# 11_-BATTERY_BACKUP.net
KiCad netlist of a schematic drawn in Altium Designer
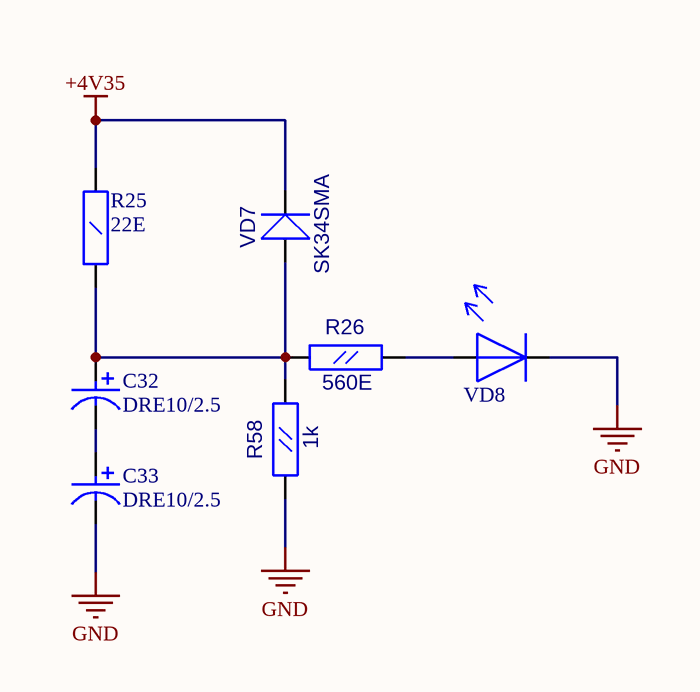
[diagram p0: [11]-BATTERY_BACKUP.SchDoc]

(export (version "E")
  (design (tool "Eeschema 10.0.6"))
  (components
    (comp (ref "C32")
      (value "DRE10/2.5")
      (footprint "CAP_D12.5_H25")
      (libsource (lib "fizik_lib") (part "SUPERCAP_10F"))
    )
    (comp (ref "C33")
      (value "DRE10/2.5")
      (footprint "CAP_D12.5_H25")
      (libsource (lib "fizik_lib") (part "SUPERCAP_10F"))
    )
    (comp (ref "R25")
      (value "22E")
      (footprint "R2512")
      (description "Resistor 2512 1W")
      (libsource (lib "fizik_lib") (part "RC2512"))
    )
    (comp (ref "R26")
      (value "560E")
      (footprint "RC0603")
      (description "RC0603")
      (libsource (lib "fizik_lib") (part "RC0603"))
    )
    (comp (ref "R58")
      (value "1k")
      (footprint "RC0603")
      (description "RC0603")
      (libsource (lib "fizik_lib") (part "RC0603"))
    )
    (comp (ref "VD7")
      (value "SK34SMA")
      (footprint "SMA")
      (description "Schottky Rectifier")
      (libsource (lib "gprs_modem") (part "SK34SMA"))
    )
    (comp (ref "VD8")
      (value "LED_0805")
      (footprint "LED0805")
      (libsource (lib "fizik_lib") (part "LED_0805"))
    )
  )
  (nets
    (net (code "1") (name "+4V35") (class "Default")
      (node (ref "R25") (pin "2") (pinfunction "B_2") (pintype "passive"))
      (node (ref "VD7") (pin "2") (pinfunction "K_2") (pintype "passive"))
    )
    (net (code "2") (name "GND") (class "Default")
      (node (ref "C33") (pin "1") (pintype "passive"))
      (node (ref "R58") (pin "1") (pinfunction "A_1") (pintype "passive"))
      (node (ref "VD8") (pin "2") (pintype "passive"))
    )
    (net (code "3") (name "Net-(C32-Pad1)") (class "Default")
      (node (ref "C32") (pin "1") (pintype "passive"))
      (node (ref "C33") (pin "2") (pintype "passive"))
    )
    (net (code "4") (name "Net-(R25-A)") (class "Default")
      (node (ref "C32") (pin "2") (pintype "passive"))
      (node (ref "R25") (pin "1") (pinfunction "A_1") (pintype "passive"))
      (node (ref "R26") (pin "1") (pinfunction "A_1") (pintype "passive"))
      (node (ref "R58") (pin "2") (pinfunction "B_2") (pintype "passive"))
      (node (ref "VD7") (pin "1") (pinfunction "A_1") (pintype "passive"))
    )
    (net (code "5") (name "Net-(R26-B)") (class "Default")
      (node (ref "R26") (pin "2") (pinfunction "B_2") (pintype "passive"))
      (node (ref "VD8") (pin "1") (pintype "passive"))
    )
  )
)
